# Arduino_Uno_V1_0.net
KiCad netlist of a schematic drawn in Altium Designer
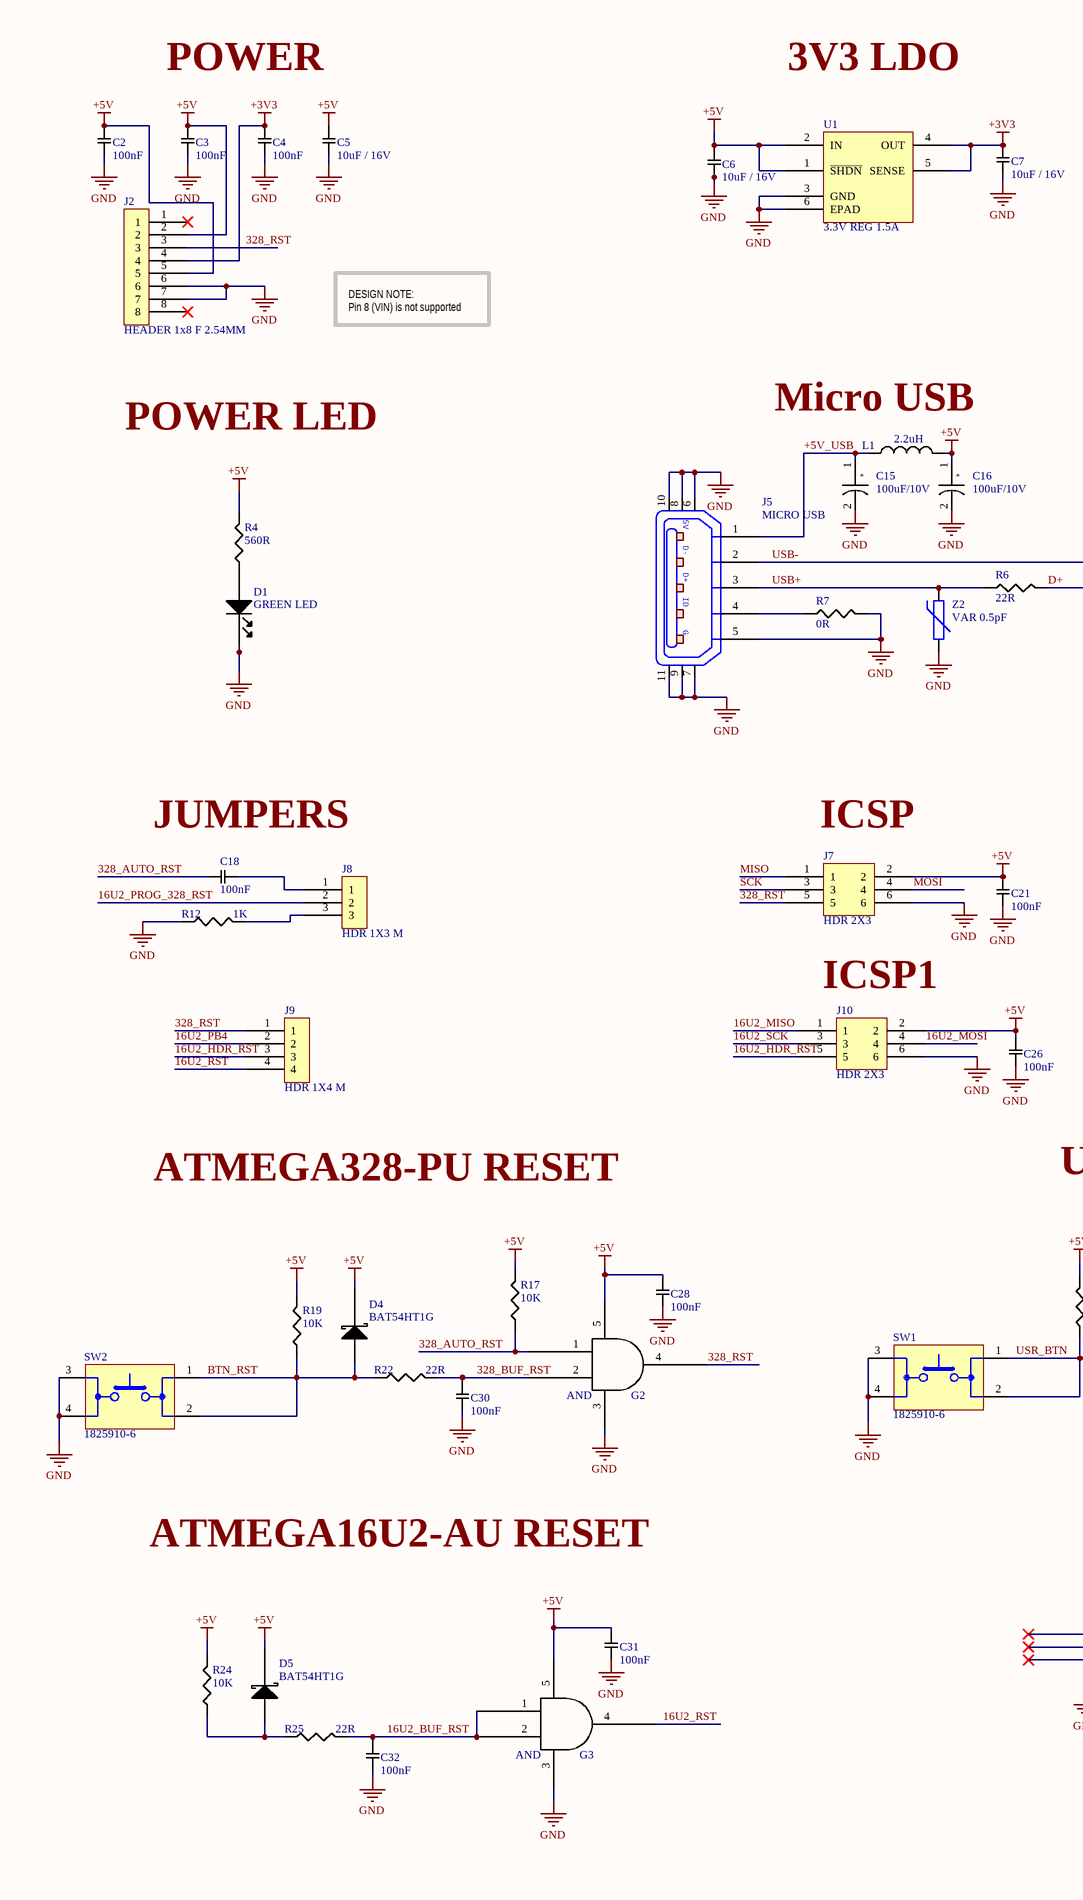
[diagram p0: Arduino_Uno_V1.0.SchDoc, left]
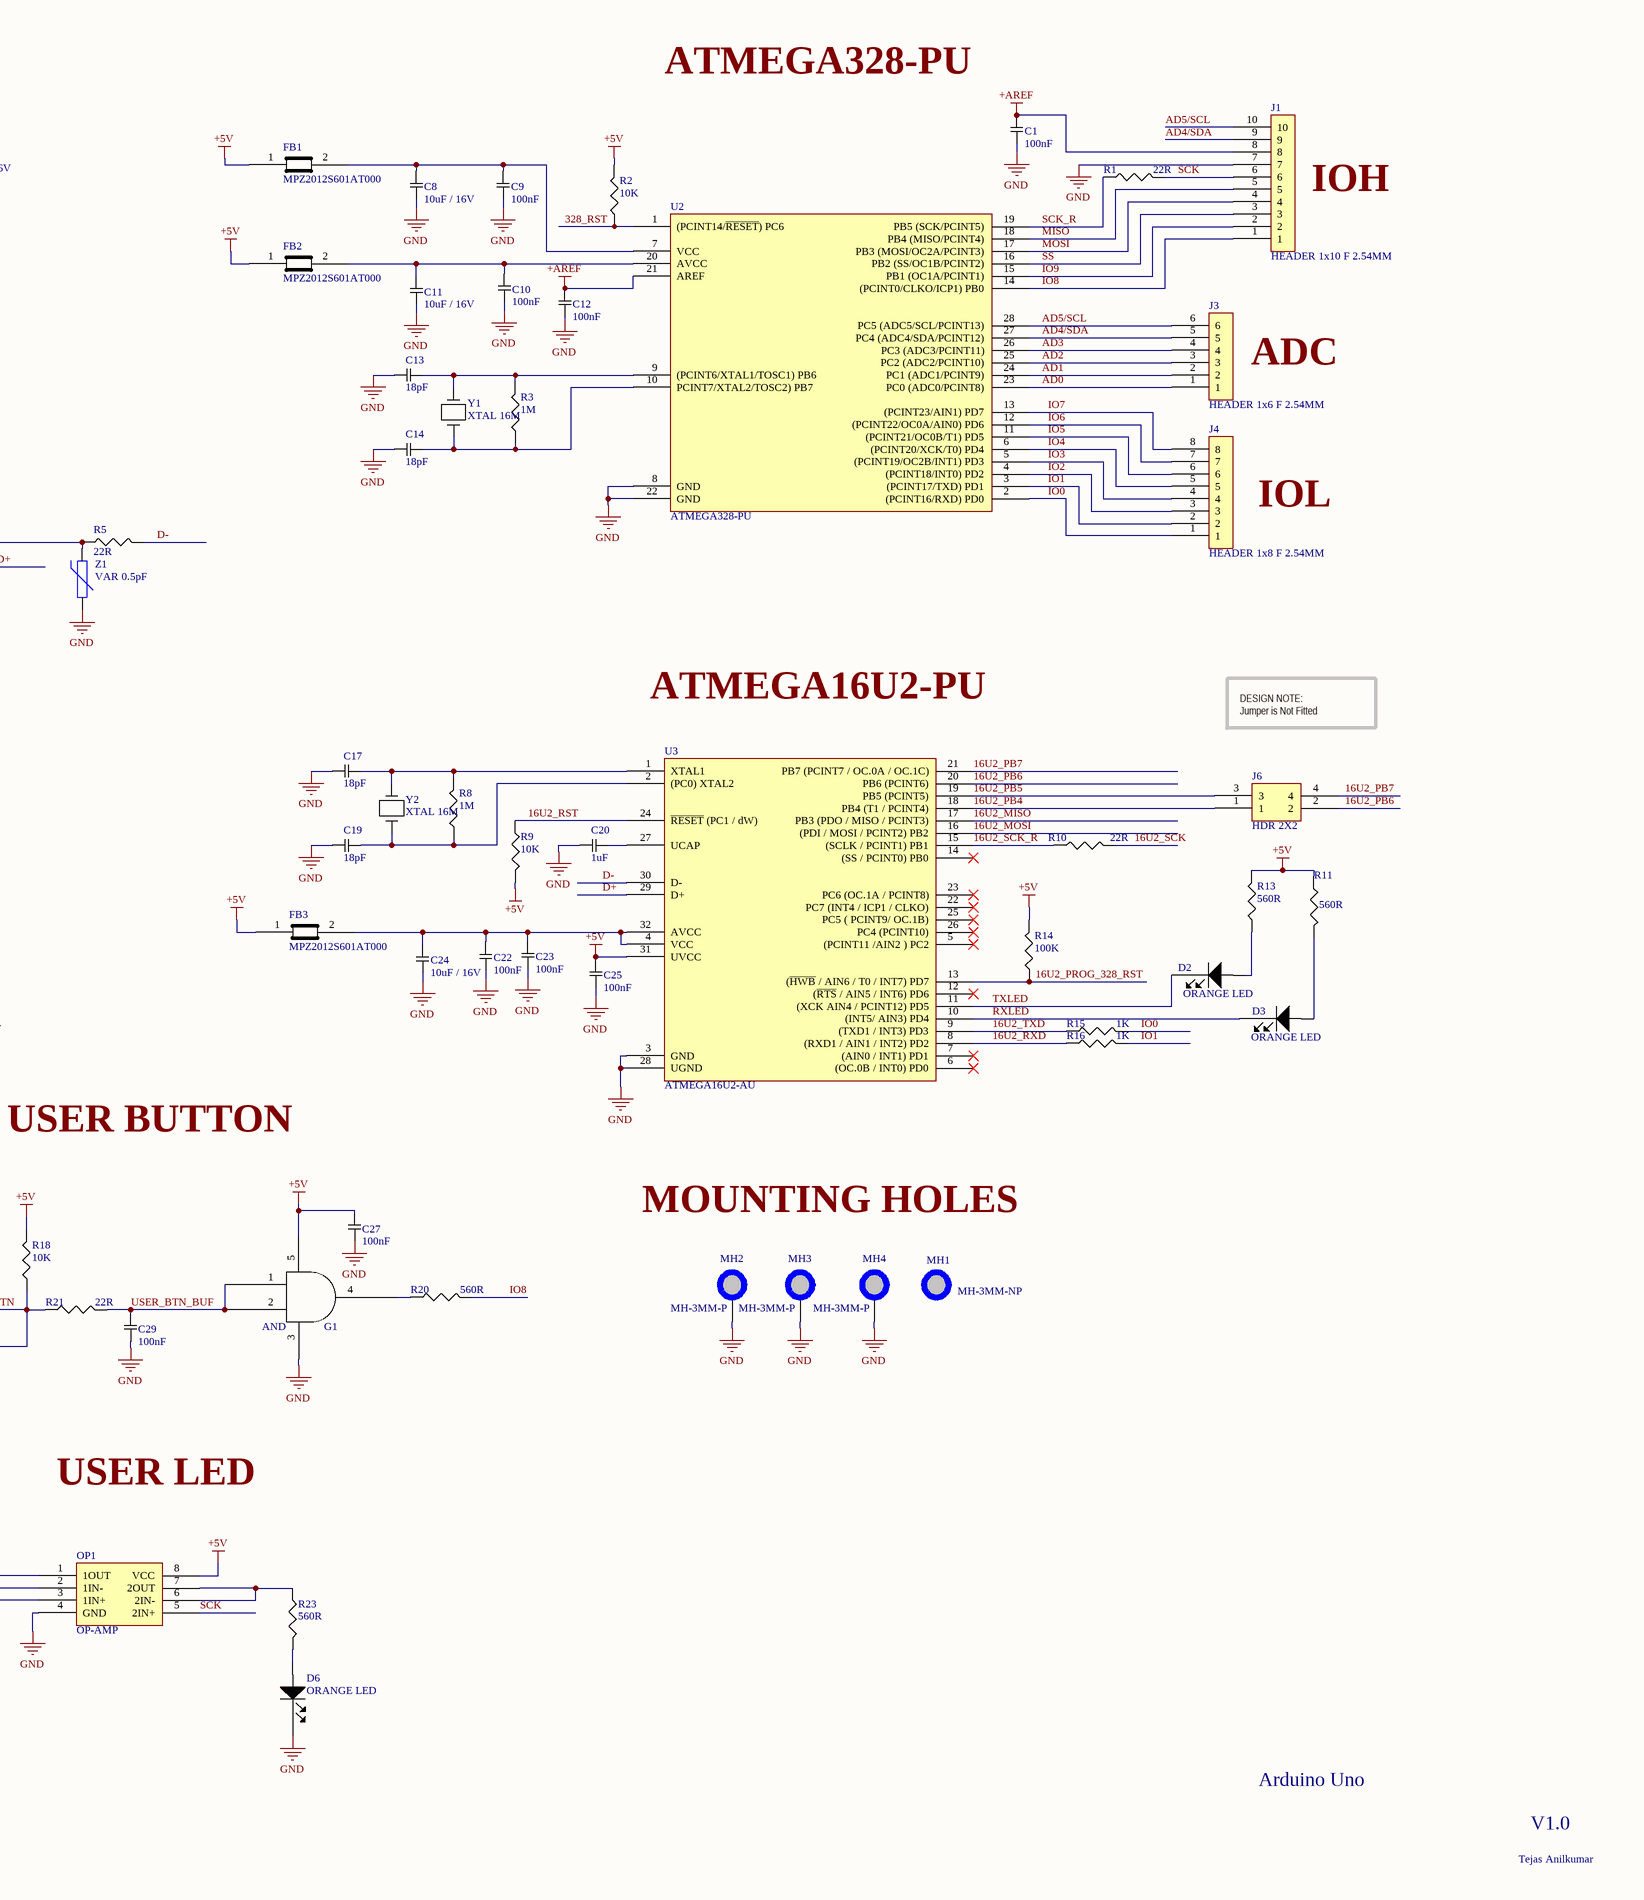
[diagram p1: Arduino_Uno_V1.0.SchDoc, right]

(export (version "E")
  (design (tool "Eeschema 10.0.6"))
  (components
    (comp (ref "C1")
      (value "100nF")
      (footprint "C0805")
      (fields
        (field (name "MANUFACTURER") "TDK")
        (field (name "MANUFACTURER PART NUMBER") "C2012X7R1H104K085AA")
        (field (name "TOLERANCE") "10%")
      )
      (libsource (lib "CAP-100n-0805") (part "C2012X7R1H104K085AA"))
    )
    (comp (ref "C2")
      (value "100nF")
      (footprint "C0805")
      (fields
        (field (name "MANUFACTURER") "TDK")
        (field (name "MANUFACTURER PART NUMBER") "C2012X7R1H104K085AA")
        (field (name "TOLERANCE") "10%")
      )
      (libsource (lib "CAP-100n-0805") (part "C2012X7R1H104K085AA"))
    )
    (comp (ref "C3")
      (value "100nF")
      (footprint "C0805")
      (fields
        (field (name "MANUFACTURER") "TDK")
        (field (name "MANUFACTURER PART NUMBER") "C2012X7R1H104K085AA")
        (field (name "TOLERANCE") "10%")
      )
      (libsource (lib "CAP-100n-0805") (part "C2012X7R1H104K085AA"))
    )
    (comp (ref "C4")
      (value "100nF")
      (footprint "C0805")
      (fields
        (field (name "MANUFACTURER") "TDK")
        (field (name "MANUFACTURER PART NUMBER") "C2012X7R1H104K085AA")
        (field (name "TOLERANCE") "10%")
      )
      (libsource (lib "CAP-100n-0805") (part "C2012X7R1H104K085AA"))
    )
    (comp (ref "C5")
      (value "10uF / 16V")
      (footprint "C0805")
      (fields
        (field (name "MANUFACTURER") "TDK")
        (field (name "MANUFACTURER PART NUMBER") "C2012X5R1C106M125AC")
        (field (name "TOLERANCE") "20%")
      )
      (libsource (lib "CAP-10u-0805") (part "C2012X5R1C106M125AC"))
    )
    (comp (ref "C6")
      (value "10uF / 16V")
      (footprint "C0805")
      (fields
        (field (name "MANUFACTURER") "TDK")
        (field (name "MANUFACTURER PART NUMBER") "C2012X5R1C106M125AC")
        (field (name "TOLERANCE") "20%")
      )
      (libsource (lib "CAP-10u-0805") (part "C2012X5R1C106M125AC"))
    )
    (comp (ref "C7")
      (value "10uF / 16V")
      (footprint "C0805")
      (fields
        (field (name "MANUFACTURER") "TDK")
        (field (name "MANUFACTURER PART NUMBER") "C2012X5R1C106M125AC")
        (field (name "TOLERANCE") "20%")
      )
      (libsource (lib "CAP-10u-0805") (part "C2012X5R1C106M125AC"))
    )
    (comp (ref "C8")
      (value "10uF / 16V")
      (footprint "C0805")
      (fields
        (field (name "MANUFACTURER") "TDK")
        (field (name "MANUFACTURER PART NUMBER") "C2012X5R1C106M125AC")
        (field (name "TOLERANCE") "20%")
      )
      (libsource (lib "CAP-10u-0805") (part "C2012X5R1C106M125AC"))
    )
    (comp (ref "C9")
      (value "100nF")
      (footprint "C0805")
      (fields
        (field (name "MANUFACTURER") "TDK")
        (field (name "MANUFACTURER PART NUMBER") "C2012X7R1H104K085AA")
        (field (name "TOLERANCE") "10%")
      )
      (libsource (lib "CAP-100n-0805") (part "C2012X7R1H104K085AA"))
    )
    (comp (ref "C10")
      (value "100nF")
      (footprint "C0805")
      (fields
        (field (name "MANUFACTURER") "TDK")
        (field (name "MANUFACTURER PART NUMBER") "C2012X7R1H104K085AA")
        (field (name "TOLERANCE") "10%")
      )
      (libsource (lib "CAP-100n-0805") (part "C2012X7R1H104K085AA"))
    )
    (comp (ref "C11")
      (value "10uF / 16V")
      (footprint "C0805")
      (fields
        (field (name "MANUFACTURER") "TDK")
        (field (name "MANUFACTURER PART NUMBER") "C2012X5R1C106M125AC")
        (field (name "TOLERANCE") "20%")
      )
      (libsource (lib "CAP-10u-0805") (part "C2012X5R1C106M125AC"))
    )
    (comp (ref "C12")
      (value "100nF")
      (footprint "C0805")
      (fields
        (field (name "MANUFACTURER") "TDK")
        (field (name "MANUFACTURER PART NUMBER") "C2012X7R1H104K085AA")
        (field (name "TOLERANCE") "10%")
      )
      (libsource (lib "CAP-100n-0805") (part "C2012X7R1H104K085AA"))
    )
    (comp (ref "C13")
      (value "18pF")
      (footprint "C0805")
      (description "CAP CER 18PF 50V C0G/NP0 0805")
      (fields
        (field (name "MANUFACTURER") "KEMET")
        (field (name "MANUFACTURER PART NUMBER") "C0805C180J5GACTU")
      )
      (libsource (lib "CAP-18p-0805") (part "C0805C180J5GACTU"))
    )
    (comp (ref "C14")
      (value "18pF")
      (footprint "C0805")
      (description "CAP CER 18PF 50V C0G/NP0 0805")
      (fields
        (field (name "MANUFACTURER") "KEMET")
        (field (name "MANUFACTURER PART NUMBER") "C0805C180J5GACTU")
      )
      (libsource (lib "CAP-18p-0805") (part "C0805C180J5GACTU"))
    )
    (comp (ref "C15")
      (value "100uF/10V")
      (footprint "CAP-ALUM")
      (description "Cap Aluminum 100uF 10V 20% (5 X 5.4mm) SMD 50mA 1000 hr 85°C T/R")
      (fields
        (field (name "MANUFACTURER") "Panasonic")
        (field (name "MANUFACTURER PART NUMBER") "EEE-1AA101WR")
      )
      (libsource (lib "CAP-100u-POL") (part "EEE-1AA101WR"))
    )
    (comp (ref "C16")
      (value "100uF/10V")
      (footprint "CAP-ALUM")
      (description "Cap Aluminum 100uF 10V 20% (5 X 5.4mm) SMD 50mA 1000 hr 85°C T/R")
      (fields
        (field (name "MANUFACTURER") "Panasonic")
        (field (name "MANUFACTURER PART NUMBER") "EEE-1AA101WR")
      )
      (libsource (lib "CAP-100u-POL") (part "EEE-1AA101WR"))
    )
    (comp (ref "C17")
      (value "18pF")
      (footprint "C0805")
      (description "CAP CER 18PF 50V C0G/NP0 0805")
      (fields
        (field (name "MANUFACTURER") "KEMET")
        (field (name "MANUFACTURER PART NUMBER") "C0805C180J5GACTU")
      )
      (libsource (lib "CAP-18p-0805") (part "C0805C180J5GACTU"))
    )
    (comp (ref "C18")
      (value "100nF")
      (footprint "C0805")
      (fields
        (field (name "MANUFACTURER") "TDK")
        (field (name "MANUFACTURER PART NUMBER") "C2012X7R1H104K085AA")
        (field (name "TOLERANCE") "10%")
      )
      (libsource (lib "CAP-100n-0805") (part "C2012X7R1H104K085AA"))
    )
    (comp (ref "C19")
      (value "18pF")
      (footprint "C0805")
      (description "CAP CER 18PF 50V C0G/NP0 0805")
      (fields
        (field (name "MANUFACTURER") "KEMET")
        (field (name "MANUFACTURER PART NUMBER") "C0805C180J5GACTU")
      )
      (libsource (lib "CAP-18p-0805") (part "C0805C180J5GACTU"))
    )
    (comp (ref "C20")
      (value "1uF")
      (footprint "C0805")
      (fields
        (field (name "MANUFACTURER") "TDK")
        (field (name "MANUFACTURER PART NUMBER") "C2012X5R1E105K125AA")
        (field (name "TOLERANCE") "10%")
      )
      (libsource (lib "CAP-1u-0805") (part "C2012X5R1E105K125AA"))
    )
    (comp (ref "C21")
      (value "100nF")
      (footprint "C0805")
      (fields
        (field (name "MANUFACTURER") "TDK")
        (field (name "MANUFACTURER PART NUMBER") "C2012X7R1H104K085AA")
        (field (name "TOLERANCE") "10%")
      )
      (libsource (lib "CAP-100n-0805") (part "C2012X7R1H104K085AA"))
    )
    (comp (ref "C22")
      (value "100nF")
      (footprint "C0805")
      (fields
        (field (name "MANUFACTURER") "TDK")
        (field (name "MANUFACTURER PART NUMBER") "C2012X7R1H104K085AA")
        (field (name "TOLERANCE") "10%")
      )
      (libsource (lib "CAP-100n-0805") (part "C2012X7R1H104K085AA"))
    )
    (comp (ref "C23")
      (value "100nF")
      (footprint "C0805")
      (fields
        (field (name "MANUFACTURER") "TDK")
        (field (name "MANUFACTURER PART NUMBER") "C2012X7R1H104K085AA")
        (field (name "TOLERANCE") "10%")
      )
      (libsource (lib "CAP-100n-0805") (part "C2012X7R1H104K085AA"))
    )
    (comp (ref "C24")
      (value "10uF / 16V")
      (footprint "C0805")
      (fields
        (field (name "MANUFACTURER") "TDK")
        (field (name "MANUFACTURER PART NUMBER") "C2012X5R1C106M125AC")
        (field (name "TOLERANCE") "20%")
      )
      (libsource (lib "CAP-10u-0805") (part "C2012X5R1C106M125AC"))
    )
    (comp (ref "C25")
      (value "100nF")
      (footprint "C0805")
      (fields
        (field (name "MANUFACTURER") "TDK")
        (field (name "MANUFACTURER PART NUMBER") "C2012X7R1H104K085AA")
        (field (name "TOLERANCE") "10%")
      )
      (libsource (lib "CAP-100n-0805") (part "C2012X7R1H104K085AA"))
    )
    (comp (ref "C26")
      (value "100nF")
      (footprint "C0805")
      (fields
        (field (name "MANUFACTURER") "TDK")
        (field (name "MANUFACTURER PART NUMBER") "C2012X7R1H104K085AA")
        (field (name "TOLERANCE") "10%")
      )
      (libsource (lib "CAP-100n-0805") (part "C2012X7R1H104K085AA"))
    )
    (comp (ref "C27")
      (value "100nF")
      (footprint "C0805")
      (fields
        (field (name "MANUFACTURER") "TDK")
        (field (name "MANUFACTURER PART NUMBER") "C2012X7R1H104K085AA")
        (field (name "TOLERANCE") "10%")
      )
      (libsource (lib "CAP-100n-0805") (part "C2012X7R1H104K085AA"))
    )
    (comp (ref "C28")
      (value "100nF")
      (footprint "C0805")
      (fields
        (field (name "MANUFACTURER") "TDK")
        (field (name "MANUFACTURER PART NUMBER") "C2012X7R1H104K085AA")
        (field (name "TOLERANCE") "10%")
      )
      (libsource (lib "CAP-100n-0805") (part "C2012X7R1H104K085AA"))
    )
    (comp (ref "C29")
      (value "100nF")
      (footprint "C0805")
      (fields
        (field (name "MANUFACTURER") "TDK")
        (field (name "MANUFACTURER PART NUMBER") "C2012X7R1H104K085AA")
        (field (name "TOLERANCE") "10%")
      )
      (libsource (lib "CAP-100n-0805") (part "C2012X7R1H104K085AA"))
    )
    (comp (ref "C30")
      (value "100nF")
      (footprint "C0805")
      (fields
        (field (name "MANUFACTURER") "TDK")
        (field (name "MANUFACTURER PART NUMBER") "C2012X7R1H104K085AA")
        (field (name "TOLERANCE") "10%")
      )
      (libsource (lib "CAP-100n-0805") (part "C2012X7R1H104K085AA"))
    )
    (comp (ref "C31")
      (value "100nF")
      (footprint "C0805")
      (fields
        (field (name "MANUFACTURER") "TDK")
        (field (name "MANUFACTURER PART NUMBER") "C2012X7R1H104K085AA")
        (field (name "TOLERANCE") "10%")
      )
      (libsource (lib "CAP-100n-0805") (part "C2012X7R1H104K085AA"))
    )
    (comp (ref "C32")
      (value "100nF")
      (footprint "C0805")
      (fields
        (field (name "MANUFACTURER") "TDK")
        (field (name "MANUFACTURER PART NUMBER") "C2012X7R1H104K085AA")
        (field (name "TOLERANCE") "10%")
      )
      (libsource (lib "CAP-100n-0805") (part "C2012X7R1H104K085AA"))
    )
    (comp (ref "D1")
      (value "GREEN LED")
      (footprint "LED_0603_GR")
      (description "LED Uni-Color Green 572nm 2-Pin Chip 0603(1608Metric) T/R")
      (fields
        (field (name "MANUFACTURER") "Osram Opto")
        (field (name "MANUFACTURER PART NUMBER") "LGL29K-G2J1-24-Z")
      )
      (libsource (lib "GREEN-LED-SMD") (part "LGL29K-G2J1-24-Z"))
    )
    (comp (ref "D2")
      (value "ORANGE LED")
      (footprint "LED_0603_OR")
      (description "OSRAM - LO L29K-H2K1-24-Z - SMARTLED 0603 ORANGE 55AC2374")
      (fields
        (field (name "MANUFACTURER") "Osram Opto")
        (field (name "MANUFACTURER PART NUMBER") "LOL29K-H2K1-24-Z")
      )
      (libsource (lib "ORANGE-LED-SMD") (part "LOL29K-H2K1-24-Z"))
    )
    (comp (ref "D3")
      (value "ORANGE LED")
      (footprint "LED_0603_OR")
      (description "OSRAM - LO L29K-H2K1-24-Z - SMARTLED 0603 ORANGE 55AC2374")
      (fields
        (field (name "MANUFACTURER") "Osram Opto")
        (field (name "MANUFACTURER PART NUMBER") "LOL29K-H2K1-24-Z")
      )
      (libsource (lib "ORANGE-LED-SMD") (part "LOL29K-H2K1-24-Z"))
    )
    (comp (ref "D4")
      (value "BAT54HT1G")
      (footprint "SOD323")
      (description "Small Signal Schottky Diode, Single, 30 V, 200 Ma, 800 Mv, 600 Ma, 150 C")
      (fields (field (name "MANUFACTURER") "ON Semiconductor / Fairchild"))
      (libsource (lib "SCHOTTKY-DIODE-600mA-30V") (part "BAT54HT1G"))
    )
    (comp (ref "D5")
      (value "BAT54HT1G")
      (footprint "SOD323")
      (description "Small Signal Schottky Diode, Single, 30 V, 200 Ma, 800 Mv, 600 Ma, 150 C")
      (fields (field (name "MANUFACTURER") "ON Semiconductor / Fairchild"))
      (libsource (lib "SCHOTTKY-DIODE-600mA-30V") (part "BAT54HT1G"))
    )
    (comp (ref "D6")
      (value "ORANGE LED")
      (footprint "LED_0603_OR")
      (description "OSRAM - LO L29K-H2K1-24-Z - SMARTLED 0603 ORANGE 55AC2374")
      (fields
        (field (name "MANUFACTURER") "Osram Opto")
        (field (name "MANUFACTURER PART NUMBER") "LOL29K-H2K1-24-Z")
      )
      (libsource (lib "ORANGE-LED-SMD") (part "LOL29K-H2K1-24-Z"))
    )
    (comp (ref "FB1")
      (value "MPZ2012S601AT000")
      (footprint "FERRITE-BEAD-0805")
      (description "Ferrite Beads Multi-Layer Power 600Ohm 25% 100MHz 2A 100mOhm DCR 0805 T/R")
      (fields (field (name "MANUFACTURER") "TDK"))
      (libsource (lib "FERRITE-BEAD-600OHM-0805") (part "MPZ2012S601AT000"))
    )
    (comp (ref "FB2")
      (value "MPZ2012S601AT000")
      (footprint "FERRITE-BEAD-0805")
      (description "Ferrite Beads Multi-Layer Power 600Ohm 25% 100MHz 2A 100mOhm DCR 0805 T/R")
      (fields (field (name "MANUFACTURER") "TDK"))
      (libsource (lib "FERRITE-BEAD-600OHM-0805") (part "MPZ2012S601AT000"))
    )
    (comp (ref "FB3")
      (value "MPZ2012S601AT000")
      (footprint "FERRITE-BEAD-0805")
      (description "Ferrite Beads Multi-Layer Power 600Ohm 25% 100MHz 2A 100mOhm DCR 0805 T/R")
      (fields (field (name "MANUFACTURER") "TDK"))
      (libsource (lib "FERRITE-BEAD-600OHM-0805") (part "MPZ2012S601AT000"))
    )
    (comp (ref "G1")
      (value "AND")
      (footprint "SOT-23-5P")
      (description "TEXAS INSTRUMENTS - SN74AHC1G09DBVR - AND Gate, 74AHC1G09, 2 Input, 2 V to 5.5 V, SOT-23-5")
      (fields
        (field (name "MANUFACTURER") "Texas Instruments")
        (field (name "MANUFACTURER PART NUMBER") "SN74AHC1G09DBVR")
      )
      (libsource (lib "AND-1CH-SOT23") (part "SN74AHC1G09DBVR"))
    )
    (comp (ref "G2")
      (value "AND")
      (footprint "SOT-23-5P")
      (description "TEXAS INSTRUMENTS - SN74AHC1G09DBVR - AND Gate, 74AHC1G09, 2 Input, 2 V to 5.5 V, SOT-23-5")
      (fields
        (field (name "MANUFACTURER") "Texas Instruments")
        (field (name "MANUFACTURER PART NUMBER") "SN74AHC1G09DBVR")
      )
      (libsource (lib "AND-1CH-SOT23") (part "SN74AHC1G09DBVR"))
    )
    (comp (ref "G3")
      (value "AND")
      (footprint "SOT-23-5P")
      (description "TEXAS INSTRUMENTS - SN74AHC1G09DBVR - AND Gate, 74AHC1G09, 2 Input, 2 V to 5.5 V, SOT-23-5")
      (fields
        (field (name "MANUFACTURER") "Texas Instruments")
        (field (name "MANUFACTURER PART NUMBER") "SN74AHC1G09DBVR")
      )
      (libsource (lib "AND-1CH-SOT23") (part "SN74AHC1G09DBVR"))
    )
    (comp (ref "J1")
      (value "HEADER 1x10 F 2.54MM")
      (footprint "HEADER-10F2.54MM")
      (fields (field (name "MANUFACTURER") "Harwin") (field (name "MANUFACTURER PART NUMBER") "M20-7821046"))
      (libsource (lib "HEADER-10PINF-2.54MM") (part "M20-7821046"))
    )
    (comp (ref "J2")
      (value "HEADER 1x8 F 2.54MM")
      (footprint "HDR-1x8-F-2.54MM")
      (description "2.54mm (0.1\") Pitch SIL Vertical PC Tail Socket Assembly, selective gold + tin, 8 contacts")
      (fields (field (name "MANUFACTURER") "Harwin") (field (name "MANUFACTURER PART NUMBER") "M20-7820842"))
      (libsource (lib "HEADER-8PINF-2.54MM") (part "M20-7820842"))
    )
    (comp (ref "J3")
      (value "HEADER 1x6 F 2.54MM")
      (footprint "HEADER-6PINF-2.54MM")
      (description "06-WAY SIL VERT SOCKET L/FREE")
      (fields (field (name "MANUFACTURER") "Harwin") (field (name "MANUFACTURER PART NUMBER") "M20-7820646"))
      (libsource (lib "HEADER-6PINF-2.54MM") (part "M20-7820646"))
    )
    (comp (ref "J4")
      (value "HEADER 1x8 F 2.54MM")
      (footprint "HDR-1x8-F-2.54MM")
      (description "2.54mm (0.1\") Pitch SIL Vertical PC Tail Socket Assembly, selective gold + tin, 8 contacts")
      (fields (field (name "MANUFACTURER") "Harwin") (field (name "MANUFACTURER PART NUMBER") "M20-7820842"))
      (libsource (lib "") (part "M20-7820842_1"))
    )
    (comp (ref "J5")
      (value "MICRO USB")
      (footprint "MICRO-USB")
      (description "CONN USB MICRO B RECPT SMT R/A")
      (fields
        (field (name "MANUFACTURER") "Amphenol ICC / FCI")
        (field (name "MANUFACTURER PART NUMBER") "10118193-0001LF")
      )
      (libsource (lib "MICRO-USB-CONNECTOR") (part "10118193-0001LF"))
    )
    (comp (ref "J6")
      (value "HDR 2X2")
      (footprint "HDR-2X2-2.54MM")
      (description "CONN HEADER 4POS .100 STR 15AU")
      (fields
        (field (name "MANUFACTURER") "Amphenol ICC / FCI")
        (field (name "MANUFACTURER PART NUMBER") "68602-204HLF")
      )
      (libsource (lib "BERGSTIK-4PIN-2R-2.54MM") (part "68602-204HLF"))
    )
    (comp (ref "J7")
      (value "HDR 2X3")
      (footprint "BERGSTIK-2X3-2.54MM")
      (description "Conn Unshrouded Header HDR 6 POS 2.54mm Solder ST Top Entry Thru-Hole BergStik® Bulk")
      (fields
        (field (name "MANUFACTURER") "Amphenol ICC / FCI")
        (field (name "MANUFACTURER PART NUMBER") "67997-106HLF")
      )
      (libsource (lib "BERGSTIK-6PIN-2R-2.54MM") (part "67997-106HLF"))
    )
    (comp (ref "J8")
      (value "HDR 1X3 M")
      (footprint "HDR 3P-M-2.54MM")
      (fields
        (field (name "MANUFACTURER") "Amphenol ICC")
        (field (name "MANUFACTURER PART NUMBER") "68000-103HLF")
      )
      (libsource (lib "HEADER-3PINM-2.54MM") (part "68000-103HLF"))
    )
    (comp (ref "J9")
      (value "HDR 1X4 M")
      (footprint "HDR 1x4 M")
      (description "Conn Unshrouded Header HDR 4 POS 2.54mm Solder ST Thru-Hole Bag")
      (fields
        (field (name "MANUFACTURER") "Amphenol ICC")
        (field (name "MANUFACTURER PART NUMBER") "68001-204HLF")
      )
      (libsource (lib "HEADER-4PINM-2.54MM") (part "68001-204HLF"))
    )
    (comp (ref "J10")
      (value "HDR 2X3")
      (footprint "BERGSTIK-2X3-2.54MM")
      (description "Conn Unshrouded Header HDR 6 POS 2.54mm Solder ST Top Entry Thru-Hole BergStik® Bulk")
      (fields
        (field (name "MANUFACTURER") "Amphenol ICC / FCI")
        (field (name "MANUFACTURER PART NUMBER") "67997-106HLF")
      )
      (libsource (lib "BERGSTIK-6PIN-2R-2.54MM") (part "67997-106HLF"))
    )
    (comp (ref "L1")
      (value "2.2uH")
      (footprint "IND-1210")
      (description "KEMET         L1210R2R2MDWIT             Product Range:L-DWI Series")
      (fields
        (field (name "MANUFACTURER") "KEMET")
        (field (name "MANUFACTURER PART NUMBER") "L1210R2R2MDWIT")
      )
      (libsource (lib "IND-2.2uH-1210") (part "L1210R2R2MDWIT"))
    )
    (comp (ref "MH1")
      (value "MH-3MM-NP")
      (footprint "MH-3MM-NP")
      (description "Mounting Hole 3mm Non-Plated")
      (libsource (lib "MOUNTING-HOLES-NON-PLATED-3MM") (part "MH-3MM NP"))
    )
    (comp (ref "MH2")
      (value "MH-3MM-P")
      (footprint "MH-3MM")
      (description "3MM Mounting Holes Plated")
      (libsource (lib "MOUNTING-HOLES-PLATED-3MM") (part "MH-3MM P"))
    )
    (comp (ref "MH3")
      (value "MH-3MM-P")
      (footprint "MH-3MM")
      (description "3MM Mounting Holes Plated")
      (libsource (lib "MOUNTING-HOLES-PLATED-3MM") (part "MH-3MM P"))
    )
    (comp (ref "MH4")
      (value "MH-3MM-P")
      (footprint "MH-3MM")
      (description "3MM Mounting Holes Plated")
      (libsource (lib "MOUNTING-HOLES-PLATED-3MM") (part "MH-3MM P"))
    )
    (comp (ref "OP1")
      (value "OP-AMP")
      (footprint "SOP8")
      (description "TEXAS INSTRUMENTS - LMV358IDGKR - OP AMP, LOW VOLTAGE, 1MHZ, 1V/US, MSOP-8")
      (fields
        (field (name "MANUFACTURER") "Texas Instruments")
        (field (name "MANUFACTURER PART NUMBER") "LMV358IDGKR")
      )
      (libsource (lib "OPAMP-LMV358-2CH-8PIN") (part "LMV358IDGKR"))
    )
    (comp (ref "R1")
      (value "22R")
      (footprint "R0805")
      (description "RES SMD 22 OHM 1% 1/8W 0805")
      (fields
        (field (name "MANUFACTURER") "Yageo")
        (field (name "MANUFACTURER PART NUMBER") "RC0805FR-0722RL")
      )
      (libsource (lib "RES-22R-0805") (part "RC0805FR-0722RL"))
    )
    (comp (ref "R2")
      (value "10K")
      (footprint "R0805")
      (description "RES SMD 10K OHM 1% 1/8W 0805")
      (fields
        (field (name "MANUFACTURER") "Yageo")
        (field (name "MANUFACTURER PART NUMBER") "RC0805FR-0710KL")
      )
      (libsource (lib "RES-10K-0805") (part "RC0805FR-0710KL"))
    )
    (comp (ref "R3")
      (value "1M")
      (footprint "R0805")
      (description "RES SMD 1M OHM 1% 1/8W 0805")
      (fields
        (field (name "MANUFACTURER") "Yageo")
        (field (name "MANUFACTURER PART NUMBER") "RC0805FR-071ML")
      )
      (libsource (lib "RES-1M-0805") (part "RC0805FR-071ML"))
    )
    (comp (ref "R4")
      (value "560R")
      (footprint "R0805")
      (description "Surface Mount Thick Film Resistor, RC Series, 560 ohm, 125 mW, - 1%, 150 V, 0805 [2012 Metric]")
      (fields
        (field (name "MANUFACTURER") "Yageo")
        (field (name "MANUFACTURER PART NUMBER") "RC0805FR-07560RL")
      )
      (libsource (lib "RES-560R-0805") (part "RC0805FR-07560RL"))
    )
    (comp (ref "R5")
      (value "22R")
      (footprint "R0805")
      (description "RES SMD 22 OHM 1% 1/8W 0805")
      (fields
        (field (name "MANUFACTURER") "Yageo")
        (field (name "MANUFACTURER PART NUMBER") "RC0805FR-0722RL")
      )
      (libsource (lib "RES-22R-0805") (part "RC0805FR-0722RL"))
    )
    (comp (ref "R6")
      (value "22R")
      (footprint "R0805")
      (description "RES SMD 22 OHM 1% 1/8W 0805")
      (fields
        (field (name "MANUFACTURER") "Yageo")
        (field (name "MANUFACTURER PART NUMBER") "RC0805FR-0722RL")
      )
      (libsource (lib "RES-22R-0805") (part "RC0805FR-0722RL"))
    )
    (comp (ref "R7")
      (value "0R")
      (footprint "R0805")
      (description "Surface Mount Thick Film Resistor, RC Series, 125 mW, - 5%, 150 V, 0805 [2012 Metric]")
      (fields
        (field (name "MANUFACTURER") "Yageo")
        (field (name "MANUFACTURER PART NUMBER") "RC0805JR-070RL")
      )
      (libsource (lib "RES-0R-0805") (part "RC0805JR-070RL"))
    )
    (comp (ref "R8")
      (value "1M")
      (footprint "R0805")
      (description "RES SMD 1M OHM 1% 1/8W 0805")
      (fields
        (field (name "MANUFACTURER") "Yageo")
        (field (name "MANUFACTURER PART NUMBER") "RC0805FR-071ML")
      )
      (libsource (lib "RES-1M-0805") (part "RC0805FR-071ML"))
    )
    (comp (ref "R9")
      (value "10K")
      (footprint "R0805")
      (description "RES SMD 10K OHM 1% 1/8W 0805")
      (fields
        (field (name "MANUFACTURER") "Yageo")
        (field (name "MANUFACTURER PART NUMBER") "RC0805FR-0710KL")
      )
      (libsource (lib "RES-10K-0805") (part "RC0805FR-0710KL"))
    )
    (comp (ref "R10")
      (value "22R")
      (footprint "R0805")
      (description "RES SMD 22 OHM 1% 1/8W 0805")
      (fields
        (field (name "MANUFACTURER") "Yageo")
        (field (name "MANUFACTURER PART NUMBER") "RC0805FR-0722RL")
      )
      (libsource (lib "RES-22R-0805") (part "RC0805FR-0722RL"))
    )
    (comp (ref "R11")
      (value "560R")
      (footprint "R0805")
      (description "Surface Mount Thick Film Resistor, RC Series, 560 ohm, 125 mW, - 1%, 150 V, 0805 [2012 Metric]")
      (fields
        (field (name "MANUFACTURER") "Yageo")
        (field (name "MANUFACTURER PART NUMBER") "RC0805FR-07560RL")
      )
      (libsource (lib "RES-560R-0805") (part "RC0805FR-07560RL"))
    )
    (comp (ref "R12")
      (value "1K")
      (footprint "R0805")
      (description "RES SMD 1K OHM 1% 1/8W 0805")
      (fields
        (field (name "MANUFACTURER") "Yageo")
        (field (name "MANUFACTURER PART NUMBER") "RC0805FR-071KL")
      )
      (libsource (lib "RES-1K-0805") (part "RC0805FR-071KL"))
    )
    (comp (ref "R13")
      (value "560R")
      (footprint "R0805")
      (description "Surface Mount Thick Film Resistor, RC Series, 560 ohm, 125 mW, - 1%, 150 V, 0805 [2012 Metric]")
      (fields
        (field (name "MANUFACTURER") "Yageo")
        (field (name "MANUFACTURER PART NUMBER") "RC0805FR-07560RL")
      )
      (libsource (lib "RES-560R-0805") (part "RC0805FR-07560RL"))
    )
    (comp (ref "R14")
      (value "100K")
      (footprint "R0805")
      (description "Res Thick Film 0805 100K Ohm 1% 1/8W ±100ppm/°C Molded SMD Paper T/R")
      (fields
        (field (name "MANUFACTURER") "Yageo")
        (field (name "MANUFACTURER PART NUMBER") "RC0805FR-07100KL")
      )
      (libsource (lib "RES-100K-0805") (part "RC0805FR-07100KL"))
    )
    (comp (ref "R15")
      (value "1K")
      (footprint "R0805")
      (description "RES SMD 1K OHM 1% 1/8W 0805")
      (fields
        (field (name "MANUFACTURER") "Yageo")
        (field (name "MANUFACTURER PART NUMBER") "RC0805FR-071KL")
      )
      (libsource (lib "RES-1K-0805") (part "RC0805FR-071KL"))
    )
    (comp (ref "R16")
      (value "1K")
      (footprint "R0805")
      (description "RES SMD 1K OHM 1% 1/8W 0805")
      (fields
        (field (name "MANUFACTURER") "Yageo")
        (field (name "MANUFACTURER PART NUMBER") "RC0805FR-071KL")
      )
      (libsource (lib "RES-1K-0805") (part "RC0805FR-071KL"))
    )
    (comp (ref "R17")
      (value "10K")
      (footprint "R0805")
      (description "RES SMD 10K OHM 1% 1/8W 0805")
      (fields
        (field (name "MANUFACTURER") "Yageo")
        (field (name "MANUFACTURER PART NUMBER") "RC0805FR-0710KL")
      )
      (libsource (lib "RES-10K-0805") (part "RC0805FR-0710KL"))
    )
    (comp (ref "R18")
      (value "10K")
      (footprint "R0805")
      (description "RES SMD 10K OHM 1% 1/8W 0805")
      (fields
        (field (name "MANUFACTURER") "Yageo")
        (field (name "MANUFACTURER PART NUMBER") "RC0805FR-0710KL")
      )
      (libsource (lib "RES-10K-0805") (part "RC0805FR-0710KL"))
    )
    (comp (ref "R19")
      (value "10K")
      (footprint "R0805")
      (description "RES SMD 10K OHM 1% 1/8W 0805")
      (fields
        (field (name "MANUFACTURER") "Yageo")
        (field (name "MANUFACTURER PART NUMBER") "RC0805FR-0710KL")
      )
      (libsource (lib "RES-10K-0805") (part "RC0805FR-0710KL"))
    )
    (comp (ref "R20")
      (value "560R")
      (footprint "R0805")
      (description "Surface Mount Thick Film Resistor, RC Series, 560 ohm, 125 mW, - 1%, 150 V, 0805 [2012 Metric]")
      (fields
        (field (name "MANUFACTURER") "Yageo")
        (field (name "MANUFACTURER PART NUMBER") "RC0805FR-07560RL")
      )
      (libsource (lib "RES-560R-0805") (part "RC0805FR-07560RL"))
    )
    (comp (ref "R21")
      (value "22R")
      (footprint "R0805")
      (description "RES SMD 22 OHM 1% 1/8W 0805")
      (fields
        (field (name "MANUFACTURER") "Yageo")
        (field (name "MANUFACTURER PART NUMBER") "RC0805FR-0722RL")
      )
      (libsource (lib "RES-22R-0805") (part "RC0805FR-0722RL"))
    )
    (comp (ref "R22")
      (value "22R")
      (footprint "R0805")
      (description "RES SMD 22 OHM 1% 1/8W 0805")
      (fields
        (field (name "MANUFACTURER") "Yageo")
        (field (name "MANUFACTURER PART NUMBER") "RC0805FR-0722RL")
      )
      (libsource (lib "RES-22R-0805") (part "RC0805FR-0722RL"))
    )
    (comp (ref "R23")
      (value "560R")
      (footprint "R0805")
      (description "Surface Mount Thick Film Resistor, RC Series, 560 ohm, 125 mW, - 1%, 150 V, 0805 [2012 Metric]")
      (fields
        (field (name "MANUFACTURER") "Yageo")
        (field (name "MANUFACTURER PART NUMBER") "RC0805FR-07560RL")
      )
      (libsource (lib "RES-560R-0805") (part "RC0805FR-07560RL"))
    )
    (comp (ref "R24")
      (value "10K")
      (footprint "R0805")
      (description "RES SMD 10K OHM 1% 1/8W 0805")
      (fields
        (field (name "MANUFACTURER") "Yageo")
        (field (name "MANUFACTURER PART NUMBER") "RC0805FR-0710KL")
      )
      (libsource (lib "RES-10K-0805") (part "RC0805FR-0710KL"))
    )
    (comp (ref "R25")
      (value "22R")
      (footprint "R0805")
      (description "RES SMD 22 OHM 1% 1/8W 0805")
      (fields
        (field (name "MANUFACTURER") "Yageo")
        (field (name "MANUFACTURER PART NUMBER") "RC0805FR-0722RL")
      )
      (libsource (lib "RES-22R-0805") (part "RC0805FR-0722RL"))
    )
    (comp (ref "SW1")
      (value "1825910-6")
      (footprint "TAC-SW-6X6")
      (description "6X6, H5,  160G TAC.SWITCH")
      (fields (field (name "MANUFACTURER") "TE Connectivity Alcoswitch"))
      (libsource (lib "TAC-SW-6X6MM") (part "1825910-6"))
    )
    (comp (ref "SW2")
      (value "1825910-6")
      (footprint "TAC-SW-6X6")
      (description "6X6, H5,  160G TAC.SWITCH")
      (fields (field (name "MANUFACTURER") "TE Connectivity Alcoswitch"))
      (libsource (lib "TAC-SW-6X6MM") (part "1825910-6"))
    )
    (comp (ref "U1")
      (value "3.3V REG 1.5A")
      (footprint "LDO-DCQ")
      (description "IC REG LINEAR 3.3V 1.5A SOT223-6")
      (fields
        (field (name "MANUFACTURER") "Texas Instruments")
        (field (name "MANUFACTURER PART NUMBER") "TL1963A-33DCQR")
      )
      (libsource (lib "LDO-3.3V-1.5A") (part "TL1963A-33DCQR"))
    )
    (comp (ref "U2")
      (value "ATMEGA328-PU")
      (footprint "ATMEGA328-PU-DIP28 - duplicate")
      (description "MCU 8-bit ATmega AVR RISC 32KB Flash 2.5V/3.3V/5V 28-Pin PDIP")
      (fields (field (name "MANUFACTURER") "Microchip / Atmel"))
      (libsource (lib "ATMEGA328-PU") (part "ATMEGA328-PU"))
    )
    (comp (ref "U3")
      (value "ATMEGA16U2-AU")
      (footprint "TQFP32")
      (description "ATmega Series 16 KB Flash 512 B RAM 16 MHz 8-Bit Microcontroller - TQFP-32")
      (fields (field (name "MANUFACTURER") "Microchip / Atmel"))
      (libsource (lib "ATMEGA16U2-AU-TQFP32") (part "ATMEGA16U2-AU"))
    )
    (comp (ref "Y1")
      (value "XTAL 16M")
      (footprint "XTAL")
      (description "CRYSTAL 16.0000MHZ 18PF SMD")
      (fields
        (field (name "MANUFACTURER") "Abracon")
        (field (name "MANUFACTURER PART NUMBER") "ABM7-16.000MHZ-D2Y-T")
      )
      (libsource (lib "XTAL-16MHZ") (part "ABM7-16.000MHZ-D2Y-T"))
    )
    (comp (ref "Y2")
      (value "XTAL 16M")
      (footprint "XTAL")
      (description "CRYSTAL 16.0000MHZ 18PF SMD")
      (fields
        (field (name "MANUFACTURER") "Abracon")
        (field (name "MANUFACTURER PART NUMBER") "ABM7-16.000MHZ-D2Y-T")
      )
      (libsource (lib "XTAL-16MHZ") (part "ABM7-16.000MHZ-D2Y-T"))
    )
    (comp (ref "Z1")
      (value "VAR 0.5pF")
      (footprint "R0603")
      (description "VARISTOR 0603")
      (fields
        (field (name "MANUFACTURER") "Bourns")
        (field (name "MANUFACTURER PART NUMBER") "CG0603MLC-05E")
      )
      (libsource (lib "VARISTOR-0.5pF-0603") (part "CG0603MLC-05E"))
    )
    (comp (ref "Z2")
      (value "VAR 0.5pF")
      (footprint "R0603")
      (description "VARISTOR 0603")
      (fields
        (field (name "MANUFACTURER") "Bourns")
        (field (name "MANUFACTURER PART NUMBER") "CG0603MLC-05E")
      )
      (libsource (lib "VARISTOR-0.5pF-0603") (part "CG0603MLC-05E"))
    )
  )
  (nets
    (net (code "1") (name "+3V3") (class "Default")
      (node (ref "C4") (pin "2") (pinfunction "2_2") (pintype "passive"))
      (node (ref "C7") (pin "2") (pinfunction "2_2") (pintype "passive"))
      (node (ref "J2") (pin "4") (pinfunction "4_4") (pintype "passive"))
      (node (ref "U1") (pin "4") (pinfunction "OUT_4") (pintype "passive"))
      (node (ref "U1") (pin "5") (pinfunction "SENSE_5") (pintype "passive"))
    )
    (net (code "2") (name "+5V") (class "Default")
      (node (ref "C16") (pin "1") (pinfunction "1_1") (pintype "passive"))
      (node (ref "C2") (pin "2") (pinfunction "2_2") (pintype "passive"))
      (node (ref "C21") (pin "2") (pinfunction "2_2") (pintype "passive"))
      (node (ref "C25") (pin "2") (pinfunction "2_2") (pintype "passive"))
      (node (ref "C26") (pin "2") (pinfunction "2_2") (pintype "passive"))
      (node (ref "C27") (pin "2") (pinfunction "2_2") (pintype "passive"))
      (node (ref "C28") (pin "2") (pinfunction "2_2") (pintype "passive"))
      (node (ref "C3") (pin "2") (pinfunction "2_2") (pintype "passive"))
      (node (ref "C31") (pin "2") (pinfunction "2_2") (pintype "passive"))
      (node (ref "C5") (pin "2") (pinfunction "2_2") (pintype "passive"))
      (node (ref "C6") (pin "2") (pinfunction "2_2") (pintype "passive"))
      (node (ref "D4") (pin "1") (pinfunction "Cathode_1") (pintype "passive"))
      (node (ref "D5") (pin "1") (pinfunction "Cathode_1") (pintype "passive"))
      (node (ref "FB1") (pin "1") (pinfunction "1_1") (pintype "passive"))
      (node (ref "FB2") (pin "1") (pinfunction "1_1") (pintype "passive"))
      (node (ref "FB3") (pin "1") (pinfunction "1_1") (pintype "passive"))
      (node (ref "G1") (pin "5") (pinfunction "VCC_5") (pintype "power_in"))
      (node (ref "G2") (pin "5") (pinfunction "VCC_5") (pintype "power_in"))
      (node (ref "G3") (pin "5") (pinfunction "VCC_5") (pintype "power_in"))
      (node (ref "J10") (pin "2") (pinfunction "2_2") (pintype "passive"))
      (node (ref "J2") (pin "2") (pinfunction "2_2") (pintype "passive"))
      (node (ref "J2") (pin "5") (pinfunction "5_5") (pintype "passive"))
      (node (ref "J7") (pin "2") (pinfunction "2_2") (pintype "passive"))
      (node (ref "L1") (pin "2") (pinfunction "2_2") (pintype "passive"))
      (node (ref "OP1") (pin "8") (pinfunction "VCC_8") (pintype "passive"))
      (node (ref "R11") (pin "1") (pinfunction "1_1") (pintype "passive"))
      (node (ref "R13") (pin "2") (pinfunction "2_2") (pintype "passive"))
      (node (ref "R14") (pin "2") (pinfunction "2_2") (pintype "passive"))
      (node (ref "R17") (pin "2") (pinfunction "2_2") (pintype "passive"))
      (node (ref "R18") (pin "2") (pinfunction "2_2") (pintype "passive"))
      (node (ref "R19") (pin "2") (pinfunction "2_2") (pintype "passive"))
      (node (ref "R2") (pin "2") (pinfunction "2_2") (pintype "passive"))
      (node (ref "R24") (pin "2") (pinfunction "2_2") (pintype "passive"))
      (node (ref "R4") (pin "2") (pinfunction "2_2") (pintype "passive"))
      (node (ref "R9") (pin "2") (pinfunction "2_2") (pintype "passive"))
      (node (ref "U1") (pin "1") (pinfunction "~{SHDN}_1") (pintype "passive"))
      (node (ref "U1") (pin "2") (pinfunction "IN_2") (pintype "passive"))
      (node (ref "U3") (pin "31") (pinfunction "UVCC_31") (pintype "passive"))
    )
    (net (code "3") (name "+AREF") (class "Default")
      (node (ref "C1") (pin "2") (pinfunction "2_2") (pintype "passive"))
      (node (ref "C12") (pin "2") (pinfunction "2_2") (pintype "passive"))
      (node (ref "J1") (pin "8") (pinfunction "8_8") (pintype "passive"))
      (node (ref "U2") (pin "21") (pinfunction "AREF_21") (pintype "passive"))
    )
    (net (code "4") (name "/+5V_USB") (class "Default")
      (node (ref "C15") (pin "1") (pinfunction "1_1") (pintype "passive"))
      (node (ref "J5") (pin "1") (pinfunction "P1_1") (pintype "passive"))
      (node (ref "L1") (pin "1") (pinfunction "1_1") (pintype "passive"))
    )
    (net (code "5") (name "/16U2_BUF_RST") (class "Default")
      (node (ref "C32") (pin "2") (pinfunction "2_2") (pintype "passive"))
      (node (ref "G3") (pin "1") (pinfunction "A_1") (pintype "passive"))
      (node (ref "G3") (pin "2") (pinfunction "B_2") (pintype "passive"))
      (node (ref "R25") (pin "2") (pinfunction "2_2") (pintype "passive"))
    )
    (net (code "6") (name "/16U2_HDR_RST") (class "Default")
      (node (ref "J10") (pin "5") (pinfunction "5_5") (pintype "passive"))
      (node (ref "J9") (pin "3") (pinfunction "3_3") (pintype "passive"))
    )
    (net (code "7") (name "/16U2_MISO") (class "Default")
      (node (ref "J10") (pin "1") (pinfunction "1_1") (pintype "passive"))
      (node (ref "U3") (pin "17") (pinfunction "PB3_(PDO_/_MISO_/_PCINT3)_17") (pintype "passive"))
    )
    (net (code "8") (name "/16U2_MOSI") (class "Default")
      (node (ref "J10") (pin "4") (pinfunction "4_4") (pintype "passive"))
      (node (ref "U3") (pin "16") (pinfunction "(PDI_/_MOSI_/_PCINT2)_PB2_16") (pintype "passive"))
    )
    (net (code "9") (name "/16U2_PB4") (class "Default")
      (node (ref "J6") (pin "1") (pinfunction "1_1") (pintype "passive"))
      (node (ref "J9") (pin "2") (pinfunction "2_2") (pintype "passive"))
      (node (ref "U3") (pin "18") (pinfunction "PB4_(T1_/_PCINT4)_18") (pintype "passive"))
    )
    (net (code "10") (name "/16U2_PB5") (class "Default")
      (node (ref "J6") (pin "3") (pinfunction "3_3") (pintype "passive"))
      (node (ref "U3") (pin "19") (pinfunction "PB5_(PCINT5)_19") (pintype "passive"))
    )
    (net (code "11") (name "/16U2_PB6") (class "Default")
      (node (ref "J6") (pin "2") (pinfunction "2_2") (pintype "passive"))
      (node (ref "U3") (pin "20") (pinfunction "PB6_(PCINT6)_20") (pintype "passive"))
    )
    (net (code "12") (name "/16U2_PB7") (class "Default")
      (node (ref "J6") (pin "4") (pinfunction "4_4") (pintype "passive"))
      (node (ref "U3") (pin "21") (pinfunction "PB7_(PCINT7_/_OC.0A_/_OC.1C)_21") (pintype "passive"))
    )
    (net (code "13") (name "/16U2_PROG_328_RST") (class "Default")
      (node (ref "J8") (pin "2") (pinfunction "2_2") (pintype "passive"))
      (node (ref "R14") (pin "1") (pinfunction "1_1") (pintype "passive"))
      (node (ref "U3") (pin "13") (pinfunction "(~{HWB}_/_AIN6_/_T0_/_INT7)_PD7_13") (pintype "passive"))
    )
    (net (code "14") (name "/16U2_RST") (class "Default")
      (node (ref "G3") (pin "4") (pinfunction "Y_4") (pintype "passive"))
      (node (ref "J9") (pin "4") (pinfunction "4_4") (pintype "passive"))
      (node (ref "R9") (pin "1") (pinfunction "1_1") (pintype "passive"))
      (node (ref "U3") (pin "24") (pinfunction "~{RESET}_(PC1_/_dW)_24") (pintype "passive"))
    )
    (net (code "15") (name "/16U2_RXD") (class "Default")
      (node (ref "R16") (pin "1") (pinfunction "1_1") (pintype "passive"))
      (node (ref "U3") (pin "8") (pinfunction "(RXD1_/_AIN1_/_INT2)_PD2_8") (pintype "passive"))
    )
    (net (code "16") (name "/16U2_SCK") (class "Default")
      (node (ref "J10") (pin "3") (pinfunction "3_3") (pintype "passive"))
      (node (ref "R10") (pin "2") (pinfunction "2_2") (pintype "passive"))
    )
    (net (code "17") (name "/16U2_SCK_R") (class "Default")
      (node (ref "R10") (pin "1") (pinfunction "1_1") (pintype "passive"))
      (node (ref "U3") (pin "15") (pinfunction "(SCLK_/_PCINT1)_PB1_15") (pintype "passive"))
    )
    (net (code "18") (name "/16U2_TXD") (class "Default")
      (node (ref "R15") (pin "1") (pinfunction "1_1") (pintype "passive"))
      (node (ref "U3") (pin "9") (pinfunction "(TXD1_/_INT3)_PD3_9") (pintype "passive"))
    )
    (net (code "19") (name "/328_AUTO_RST") (class "Default")
      (node (ref "C18") (pin "2") (pinfunction "2_2") (pintype "passive"))
      (node (ref "G2") (pin "1") (pinfunction "A_1") (pintype "passive"))
      (node (ref "R17") (pin "1") (pinfunction "1_1") (pintype "passive"))
    )
    (net (code "20") (name "/328_BUF_RST") (class "Default")
      (node (ref "C30") (pin "2") (pinfunction "2_2") (pintype "passive"))
      (node (ref "G2") (pin "2") (pinfunction "B_2") (pintype "passive"))
      (node (ref "R22") (pin "2") (pinfunction "2_2") (pintype "passive"))
    )
    (net (code "21") (name "/328_RST") (class "Default")
      (node (ref "G2") (pin "4") (pinfunction "Y_4") (pintype "passive"))
      (node (ref "J2") (pin "3") (pinfunction "3_3") (pintype "passive"))
      (node (ref "J7") (pin "5") (pinfunction "5_5") (pintype "passive"))
      (node (ref "J9") (pin "1") (pinfunction "1_1") (pintype "passive"))
      (node (ref "R2") (pin "1") (pinfunction "1_1") (pintype "passive"))
      (node (ref "U2") (pin "1") (pinfunction "(PCINT14/~{RESET})_PC6_1") (pintype "passive"))
    )
    (net (code "22") (name "/AD0") (class "Default")
      (node (ref "J3") (pin "1") (pinfunction "1_1") (pintype "passive"))
      (node (ref "U2") (pin "23") (pinfunction "PC0_(ADC0/PCINT8)_23") (pintype "passive"))
    )
    (net (code "23") (name "/AD1") (class "Default")
      (node (ref "J3") (pin "2") (pinfunction "2_2") (pintype "passive"))
      (node (ref "U2") (pin "24") (pinfunction "PC1_(ADC1/PCINT9)_24") (pintype "passive"))
    )
    (net (code "24") (name "/AD2") (class "Default")
      (node (ref "J3") (pin "3") (pinfunction "3_3") (pintype "passive"))
      (node (ref "U2") (pin "25") (pinfunction "PC2_(ADC2/PCINT10)_25") (pintype "passive"))
    )
    (net (code "25") (name "/AD3") (class "Default")
      (node (ref "J3") (pin "4") (pinfunction "4_4") (pintype "passive"))
      (node (ref "U2") (pin "26") (pinfunction "PC3_(ADC3/PCINT11)_26") (pintype "passive"))
    )
    (net (code "26") (name "/AD4{slash}SDA") (class "Default")
      (node (ref "J1") (pin "9") (pinfunction "9_9") (pintype "passive"))
      (node (ref "J3") (pin "5") (pinfunction "5_5") (pintype "passive"))
      (node (ref "U2") (pin "27") (pinfunction "PC4_(ADC4/SDA/PCINT12)_27") (pintype "passive"))
    )
    (net (code "27") (name "/AD5{slash}SCL") (class "Default")
      (node (ref "J1") (pin "10") (pinfunction "10_10") (pintype "passive"))
      (node (ref "J3") (pin "6") (pinfunction "6_6") (pintype "passive"))
      (node (ref "U2") (pin "28") (pinfunction "PC5_(ADC5/SCL/PCINT13)_28") (pintype "passive"))
    )
    (net (code "28") (name "/BTN_RST") (class "Default")
      (node (ref "D4") (pin "2") (pinfunction "Anode_2") (pintype "passive"))
      (node (ref "R19") (pin "1") (pinfunction "1_1") (pintype "passive"))
      (node (ref "R22") (pin "1") (pinfunction "1_1") (pintype "passive"))
      (node (ref "SW2") (pin "1") (pinfunction "1_1") (pintype "passive"))
      (node (ref "SW2") (pin "2") (pinfunction "2_2") (pintype "passive"))
    )
    (net (code "29") (name "/D+") (class "Default")
      (node (ref "R6") (pin "2") (pinfunction "2_2") (pintype "passive"))
      (node (ref "U3") (pin "29") (pinfunction "D+_29") (pintype "passive"))
    )
    (net (code "30") (name "/D-") (class "Default")
      (node (ref "R5") (pin "2") (pinfunction "2_2") (pintype "passive"))
      (node (ref "U3") (pin "30") (pinfunction "D-_30") (pintype "passive"))
    )
    (net (code "31") (name "/IO0") (class "Default")
      (node (ref "J4") (pin "1") (pinfunction "1_1") (pintype "passive"))
      (node (ref "R15") (pin "2") (pinfunction "2_2") (pintype "passive"))
      (node (ref "U2") (pin "2") (pinfunction "(PCINT16/RXD)_PD0_2") (pintype "passive"))
    )
    (net (code "32") (name "/IO1") (class "Default")
      (node (ref "J4") (pin "2") (pinfunction "2_2") (pintype "passive"))
      (node (ref "R16") (pin "2") (pinfunction "2_2") (pintype "passive"))
      (node (ref "U2") (pin "3") (pinfunction "(PCINT17/TXD)_PD1_3") (pintype "passive"))
    )
    (net (code "33") (name "/IO2") (class "Default")
      (node (ref "J4") (pin "3") (pinfunction "3_3") (pintype "passive"))
      (node (ref "U2") (pin "4") (pinfunction "(PCINT18/INT0)_PD2_4") (pintype "passive"))
    )
    (net (code "34") (name "/IO3") (class "Default")
      (node (ref "J4") (pin "4") (pinfunction "4_4") (pintype "passive"))
      (node (ref "U2") (pin "5") (pinfunction "(PCINT19/OC2B/INT1)_PD3_5") (pintype "passive"))
    )
    (net (code "35") (name "/IO4") (class "Default")
      (node (ref "J4") (pin "5") (pinfunction "5_5") (pintype "passive"))
      (node (ref "U2") (pin "6") (pinfunction "(PCINT20/XCK/T0)_PD4_6") (pintype "passive"))
    )
    (net (code "36") (name "/IO5") (class "Default")
      (node (ref "J4") (pin "6") (pinfunction "6_6") (pintype "passive"))
      (node (ref "U2") (pin "11") (pinfunction "(PCINT21/OC0B/T1)_PD5_11") (pintype "passive"))
    )
    (net (code "37") (name "/IO6") (class "Default")
      (node (ref "J4") (pin "7") (pinfunction "7_7") (pintype "passive"))
      (node (ref "U2") (pin "12") (pinfunction "(PCINT22/OC0A/AIN0)_PD6_12") (pintype "passive"))
    )
    (net (code "38") (name "/IO7") (class "Default")
      (node (ref "J4") (pin "8") (pinfunction "8_8") (pintype "passive"))
      (node (ref "U2") (pin "13") (pinfunction "(PCINT23/AIN1)_PD7_13") (pintype "passive"))
    )
    (net (code "39") (name "/IO8") (class "Default")
      (node (ref "J1") (pin "1") (pinfunction "1_1") (pintype "passive"))
      (node (ref "R20") (pin "2") (pinfunction "2_2") (pintype "passive"))
      (node (ref "U2") (pin "14") (pinfunction "(PCINT0/CLKO/ICP1)_PB0_14") (pintype "passive"))
    )
    (net (code "40") (name "/IO9") (class "Default")
      (node (ref "J1") (pin "2") (pinfunction "2_2") (pintype "passive"))
      (node (ref "U2") (pin "15") (pinfunction "PB1_(OC1A/PCINT1)_15") (pintype "passive"))
    )
    (net (code "41") (name "/MISO") (class "Default")
      (node (ref "J1") (pin "5") (pinfunction "5_5") (pintype "passive"))
      (node (ref "J7") (pin "1") (pinfunction "1_1") (pintype "passive"))
      (node (ref "U2") (pin "18") (pinfunction "PB4_(MISO/PCINT4)_18") (pintype "passive"))
    )
    (net (code "42") (name "/MOSI") (class "Default")
      (node (ref "J1") (pin "4") (pinfunction "4_4") (pintype "passive"))
      (node (ref "J7") (pin "4") (pinfunction "4_4") (pintype "passive"))
      (node (ref "U2") (pin "17") (pinfunction "PB3_(MOSI/OC2A/PCINT3)_17") (pintype "passive"))
    )
    (net (code "43") (name "/RXLED") (class "Default")
      (node (ref "D3") (pin "1") (pinfunction "cathode_1") (pintype "passive"))
      (node (ref "U3") (pin "10") (pinfunction "(INT5/_AIN3)_PD4_10") (pintype "passive"))
    )
    (net (code "44") (name "/SCK") (class "Default")
      (node (ref "J1") (pin "6") (pinfunction "6_6") (pintype "passive"))
      (node (ref "J7") (pin "3") (pinfunction "3_3") (pintype "passive"))
      (node (ref "OP1") (pin "5") (pinfunction "2IN+_5") (pintype "passive"))
      (node (ref "R1") (pin "2") (pinfunction "2_2") (pintype "passive"))
    )
    (net (code "45") (name "/SCK_R") (class "Default")
      (node (ref "R1") (pin "1") (pinfunction "1_1") (pintype "passive"))
      (node (ref "U2") (pin "19") (pinfunction "PB5_(SCK/PCINT5)_19") (pintype "passive"))
    )
    (net (code "46") (name "/SS") (class "Default")
      (node (ref "J1") (pin "3") (pinfunction "3_3") (pintype "passive"))
      (node (ref "U2") (pin "16") (pinfunction "PB2_(SS/OC1B/PCINT2)_16") (pintype "passive"))
    )
    (net (code "47") (name "/TXLED") (class "Default")
      (node (ref "D2") (pin "1") (pinfunction "cathode_1") (pintype "passive"))
      (node (ref "U3") (pin "11") (pinfunction "(XCK_AIN4_/_PCINT12)_PD5_11") (pintype "passive"))
    )
    (net (code "48") (name "/USB+") (class "Default")
      (node (ref "J5") (pin "3") (pinfunction "P3_3") (pintype "passive"))
      (node (ref "R6") (pin "1") (pinfunction "1_1") (pintype "passive"))
      (node (ref "Z2") (pin "2") (pinfunction "2_2") (pintype "passive"))
    )
    (net (code "49") (name "/USB-") (class "Default")
      (node (ref "J5") (pin "2") (pinfunction "P2_2") (pintype "passive"))
      (node (ref "R5") (pin "1") (pinfunction "1_1") (pintype "passive"))
      (node (ref "Z1") (pin "2") (pinfunction "2_2") (pintype "passive"))
    )
    (net (code "50") (name "/USER_BTN_BUF") (class "Default")
      (node (ref "C29") (pin "2") (pinfunction "2_2") (pintype "passive"))
      (node (ref "G1") (pin "1") (pinfunction "A_1") (pintype "passive"))
      (node (ref "G1") (pin "2") (pinfunction "B_2") (pintype "passive"))
      (node (ref "R21") (pin "2") (pinfunction "2_2") (pintype "passive"))
    )
    (net (code "51") (name "/USR_BTN") (class "Default")
      (node (ref "R18") (pin "1") (pinfunction "1_1") (pintype "passive"))
      (node (ref "R21") (pin "1") (pinfunction "1_1") (pintype "passive"))
      (node (ref "SW1") (pin "1") (pinfunction "1_1") (pintype "passive"))
      (node (ref "SW1") (pin "2") (pinfunction "2_2") (pintype "passive"))
    )
    (net (code "52") (name "GND") (class "Default")
      (node (ref "C1") (pin "1") (pinfunction "1_1") (pintype "passive"))
      (node (ref "C10") (pin "1") (pinfunction "1_1") (pintype "passive"))
      (node (ref "C11") (pin "1") (pinfunction "1_1") (pintype "passive"))
      (node (ref "C12") (pin "1") (pinfunction "1_1") (pintype "passive"))
      (node (ref "C13") (pin "1") (pinfunction "1_1") (pintype "passive"))
      (node (ref "C14") (pin "1") (pinfunction "1_1") (pintype "passive"))
      (node (ref "C15") (pin "2") (pinfunction "2_2") (pintype "passive"))
      (node (ref "C16") (pin "2") (pinfunction "2_2") (pintype "passive"))
      (node (ref "C17") (pin "1") (pinfunction "1_1") (pintype "passive"))
      (node (ref "C19") (pin "1") (pinfunction "1_1") (pintype "passive"))
      (node (ref "C2") (pin "1") (pinfunction "1_1") (pintype "passive"))
      (node (ref "C20") (pin "1") (pinfunction "1_1") (pintype "passive"))
      (node (ref "C21") (pin "1") (pinfunction "1_1") (pintype "passive"))
      (node (ref "C22") (pin "1") (pinfunction "1_1") (pintype "passive"))
      (node (ref "C23") (pin "1") (pinfunction "1_1") (pintype "passive"))
      (node (ref "C24") (pin "1") (pinfunction "1_1") (pintype "passive"))
      (node (ref "C25") (pin "1") (pinfunction "1_1") (pintype "passive"))
      (node (ref "C26") (pin "1") (pinfunction "1_1") (pintype "passive"))
      (node (ref "C27") (pin "1") (pinfunction "1_1") (pintype "passive"))
      (node (ref "C28") (pin "1") (pinfunction "1_1") (pintype "passive"))
      (node (ref "C29") (pin "1") (pinfunction "1_1") (pintype "passive"))
      (node (ref "C3") (pin "1") (pinfunction "1_1") (pintype "passive"))
      (node (ref "C30") (pin "1") (pinfunction "1_1") (pintype "passive"))
      (node (ref "C31") (pin "1") (pinfunction "1_1") (pintype "passive"))
      (node (ref "C32") (pin "1") (pinfunction "1_1") (pintype "passive"))
      (node (ref "C4") (pin "1") (pinfunction "1_1") (pintype "passive"))
      (node (ref "C5") (pin "1") (pinfunction "1_1") (pintype "passive"))
      (node (ref "C6") (pin "1") (pinfunction "1_1") (pintype "passive"))
      (node (ref "C7") (pin "1") (pinfunction "1_1") (pintype "passive"))
      (node (ref "C8") (pin "1") (pinfunction "1_1") (pintype "passive"))
      (node (ref "C9") (pin "1") (pinfunction "1_1") (pintype "passive"))
      (node (ref "D1") (pin "1") (pinfunction "cathode_1") (pintype "passive"))
      (node (ref "D6") (pin "1") (pinfunction "cathode_1") (pintype "passive"))
      (node (ref "G1") (pin "3") (pinfunction "GND_3") (pintype "power_in"))
      (node (ref "G2") (pin "3") (pinfunction "GND_3") (pintype "power_in"))
      (node (ref "G3") (pin "3") (pinfunction "GND_3") (pintype "power_in"))
      (node (ref "J1") (pin "7") (pinfunction "7_7") (pintype "passive"))
      (node (ref "J10") (pin "6") (pinfunction "6_6") (pintype "passive"))
      (node (ref "J2") (pin "6") (pinfunction "6_6") (pintype "passive"))
      (node (ref "J2") (pin "7") (pinfunction "7_7") (pintype "passive"))
      (node (ref "J5") (pin "10") (pinfunction "10_10") (pintype "passive"))
      (node (ref "J5") (pin "11") (pinfunction "11_11") (pintype "passive"))
      (node (ref "J5") (pin "5") (pinfunction "P5_5") (pintype "passive"))
      (node (ref "J5") (pin "6") (pinfunction "6_6") (pintype "passive"))
      (node (ref "J5") (pin "7") (pinfunction "7_7") (pintype "passive"))
      (node (ref "J5") (pin "8") (pinfunction "8_8") (pintype "passive"))
      (node (ref "J5") (pin "9") (pinfunction "9_9") (pintype "passive"))
      (node (ref "J7") (pin "6") (pinfunction "6_6") (pintype "passive"))
      (node (ref "MH2") (pin "1") (pinfunction "1_1") (pintype "passive"))
      (node (ref "MH3") (pin "1") (pinfunction "1_1") (pintype "passive"))
      (node (ref "MH4") (pin "1") (pinfunction "1_1") (pintype "passive"))
      (node (ref "OP1") (pin "4") (pinfunction "GND_4") (pintype "passive"))
      (node (ref "R12") (pin "1") (pinfunction "1_1") (pintype "passive"))
      (node (ref "R7") (pin "2") (pinfunction "2_2") (pintype "passive"))
      (node (ref "SW1") (pin "3") (pinfunction "MECH1_3") (pintype "passive"))
      (node (ref "SW1") (pin "4") (pinfunction "MECH2_4") (pintype "passive"))
      (node (ref "SW2") (pin "3") (pinfunction "MECH1_3") (pintype "passive"))
      (node (ref "SW2") (pin "4") (pinfunction "MECH2_4") (pintype "passive"))
      (node (ref "U1") (pin "3") (pinfunction "GND_3") (pintype "passive"))
      (node (ref "U1") (pin "6") (pinfunction "EPAD_6") (pintype "passive"))
      (node (ref "U2") (pin "22") (pinfunction "GND_22") (pintype "passive"))
      (node (ref "U2") (pin "8") (pinfunction "GND_8") (pintype "passive"))
      (node (ref "U3") (pin "28") (pinfunction "UGND_28") (pintype "passive"))
      (node (ref "U3") (pin "3") (pinfunction "GND_3") (pintype "passive"))
      (node (ref "Z1") (pin "1") (pinfunction "1_1") (pintype "passive"))
      (node (ref "Z2") (pin "1") (pinfunction "1_1") (pintype "passive"))
    )
    (net (code "53") (name "Net-(C18-Pad1)") (class "Default")
      (node (ref "C18") (pin "1") (pinfunction "1_1") (pintype "passive"))
      (node (ref "J8") (pin "1") (pinfunction "1_1") (pintype "passive"))
    )
    (net (code "54") (name "Net-(D1-ANODE)") (class "Default")
      (node (ref "D1") (pin "2") (pinfunction "ANODE_2") (pintype "passive"))
      (node (ref "R4") (pin "1") (pinfunction "1_1") (pintype "passive"))
    )
    (net (code "55") (name "Net-(D2-ANODE)") (class "Default")
      (node (ref "D2") (pin "2") (pinfunction "ANODE_2") (pintype "passive"))
      (node (ref "R13") (pin "1") (pinfunction "1_1") (pintype "passive"))
    )
    (net (code "56") (name "Net-(D3-ANODE)") (class "Default")
      (node (ref "D3") (pin "2") (pinfunction "ANODE_2") (pintype "passive"))
      (node (ref "R11") (pin "2") (pinfunction "2_2") (pintype "passive"))
    )
    (net (code "57") (name "Net-(D5-Anode)") (class "Default")
      (node (ref "D5") (pin "2") (pinfunction "Anode_2") (pintype "passive"))
      (node (ref "R24") (pin "1") (pinfunction "1_1") (pintype "passive"))
      (node (ref "R25") (pin "1") (pinfunction "1_1") (pintype "passive"))
    )
    (net (code "58") (name "Net-(D6-ANODE)") (class "Default")
      (node (ref "D6") (pin "2") (pinfunction "ANODE_2") (pintype "passive"))
      (node (ref "R23") (pin "2") (pinfunction "2_2") (pintype "passive"))
    )
    (net (code "59") (name "Net-(G1-Y)") (class "Default")
      (node (ref "G1") (pin "4") (pinfunction "Y_4") (pintype "passive"))
      (node (ref "R20") (pin "1") (pinfunction "1_1") (pintype "passive"))
    )
    (net (code "60") (name "Net-(J5-P4)") (class "Default")
      (node (ref "J5") (pin "4") (pinfunction "P4_4") (pintype "passive"))
      (node (ref "R7") (pin "1") (pinfunction "1_1") (pintype "passive"))
    )
    (net (code "61") (name "Net-(J8-Pad3)") (class "Default")
      (node (ref "J8") (pin "3") (pinfunction "3_3") (pintype "passive"))
      (node (ref "R12") (pin "2") (pinfunction "2_2") (pintype "passive"))
    )
    (net (code "62") (name "Net-(OP1-2IN-)") (class "Default")
      (node (ref "OP1") (pin "6") (pinfunction "2IN-_6") (pintype "passive"))
      (node (ref "OP1") (pin "7") (pinfunction "2OUT_7") (pintype "passive"))
      (node (ref "R23") (pin "1") (pinfunction "1_1") (pintype "passive"))
    )
    (net (code "63") (name "Net-(U2-(PCINT6{slash}XTAL1{slash}TOSC1)_PB6)") (class "Default")
      (node (ref "C13") (pin "2") (pinfunction "2_2") (pintype "passive"))
      (node (ref "R3") (pin "2") (pinfunction "2_2") (pintype "passive"))
      (node (ref "U2") (pin "9") (pinfunction "(PCINT6/XTAL1/TOSC1)_PB6_9") (pintype "passive"))
      (node (ref "Y1") (pin "2") (pinfunction "2_2") (pintype "passive"))
    )
    (net (code "64") (name "Net-(U2-AVCC)") (class "Default")
      (node (ref "C10") (pin "2") (pinfunction "2_2") (pintype "passive"))
      (node (ref "C11") (pin "2") (pinfunction "2_2") (pintype "passive"))
      (node (ref "FB2") (pin "2") (pinfunction "2_2") (pintype "passive"))
      (node (ref "U2") (pin "20") (pinfunction "AVCC_20") (pintype "passive"))
    )
    (net (code "65") (name "Net-(U2-PCINT7{slash}XTAL2{slash}TOSC2)_PB7)") (class "Default")
      (node (ref "C14") (pin "2") (pinfunction "2_2") (pintype "passive"))
      (node (ref "R3") (pin "1") (pinfunction "1_1") (pintype "passive"))
      (node (ref "U2") (pin "10") (pinfunction "PCINT7/XTAL2/TOSC2)_PB7_10") (pintype "passive"))
      (node (ref "Y1") (pin "1") (pinfunction "1_1") (pintype "passive"))
    )
    (net (code "66") (name "Net-(U2-VCC)") (class "Default")
      (node (ref "C8") (pin "2") (pinfunction "2_2") (pintype "passive"))
      (node (ref "C9") (pin "2") (pinfunction "2_2") (pintype "passive"))
      (node (ref "FB1") (pin "2") (pinfunction "2_2") (pintype "passive"))
      (node (ref "U2") (pin "7") (pinfunction "VCC_7") (pintype "passive"))
    )
    (net (code "67") (name "Net-(U3-(PC0)_XTAL2)") (class "Default")
      (node (ref "C19") (pin "2") (pinfunction "2_2") (pintype "passive"))
      (node (ref "R8") (pin "1") (pinfunction "1_1") (pintype "passive"))
      (node (ref "U3") (pin "2") (pinfunction "(PC0)_XTAL2_2") (pintype "passive"))
      (node (ref "Y2") (pin "1") (pinfunction "1_1") (pintype "passive"))
    )
    (net (code "68") (name "Net-(U3-AVCC)") (class "Default")
      (node (ref "C22") (pin "2") (pinfunction "2_2") (pintype "passive"))
      (node (ref "C23") (pin "2") (pinfunction "2_2") (pintype "passive"))
      (node (ref "C24") (pin "2") (pinfunction "2_2") (pintype "passive"))
      (node (ref "FB3") (pin "2") (pinfunction "2_2") (pintype "passive"))
      (node (ref "U3") (pin "32") (pinfunction "AVCC_32") (pintype "passive"))
      (node (ref "U3") (pin "4") (pinfunction "VCC_4") (pintype "passive"))
    )
    (net (code "69") (name "Net-(U3-UCAP)") (class "Default")
      (node (ref "C20") (pin "2") (pinfunction "2_2") (pintype "passive"))
      (node (ref "U3") (pin "27") (pinfunction "UCAP_27") (pintype "passive"))
    )
    (net (code "70") (name "Net-(U3-XTAL1)") (class "Default")
      (node (ref "C17") (pin "2") (pinfunction "2_2") (pintype "passive"))
      (node (ref "R8") (pin "2") (pinfunction "2_2") (pintype "passive"))
      (node (ref "U3") (pin "1") (pinfunction "XTAL1_1") (pintype "passive"))
      (node (ref "Y2") (pin "2") (pinfunction "2_2") (pintype "passive"))
    )
    (net (code "71") (name "unconnected-(J2-Pad1)") (class "Default")
      (node (ref "J2") (pin "1") (pinfunction "1_1") (pintype "passive+no_connect"))
    )
    (net (code "72") (name "unconnected-(J2-Pad8)") (class "Default")
      (node (ref "J2") (pin "8") (pinfunction "8_8") (pintype "passive+no_connect"))
    )
    (net (code "73") (name "unconnected-(OP1-1IN+-Pad3)") (class "Default")
      (node (ref "OP1") (pin "3") (pinfunction "1IN+_3") (pintype "passive+no_connect"))
    )
    (net (code "74") (name "unconnected-(OP1-1IN--Pad2)") (class "Default")
      (node (ref "OP1") (pin "2") (pinfunction "1IN-_2") (pintype "passive+no_connect"))
    )
    (net (code "75") (name "unconnected-(OP1-1OUT-Pad1)") (class "Default")
      (node (ref "OP1") (pin "1") (pinfunction "1OUT_1") (pintype "passive+no_connect"))
    )
    (net (code "76") (name "unconnected-(U3-(AIN0_{slash}_INT1)_PD1-Pad7)") (class "Default")
      (node (ref "U3") (pin "7") (pinfunction "(AIN0_/_INT1)_PD1_7") (pintype "passive+no_connect"))
    )
    (net (code "77") (name "unconnected-(U3-(OC.0B_{slash}_INT0)_PD0-Pad6)") (class "Default")
      (node (ref "U3") (pin "6") (pinfunction "(OC.0B_/_INT0)_PD0_6") (pintype "passive+no_connect"))
    )
    (net (code "78") (name "unconnected-(U3-(PCINT11_{slash}AIN2_)_PC2-Pad5)") (class "Default")
      (node (ref "U3") (pin "5") (pinfunction "(PCINT11_/AIN2_)_PC2_5") (pintype "passive+no_connect"))
    )
    (net (code "79") (name "unconnected-(U3-(SS_{slash}_PCINT0)_PB0-Pad14)") (class "Default")
      (node (ref "U3") (pin "14") (pinfunction "(SS_/_PCINT0)_PB0_14") (pintype "passive+no_connect"))
    )
    (net (code "80") (name "unconnected-(U3-(~{RTS}_{slash}_AIN5_{slash}_INT6)_PD6-Pad12)") (class "Default")
      (node (ref "U3") (pin "12") (pinfunction "(~{RTS}_/_AIN5_/_INT6)_PD6_12") (pintype "passive+no_connect"))
    )
    (net (code "81") (name "unconnected-(U3-PC4_(PCINT10)-Pad26)") (class "Default")
      (node (ref "U3") (pin "26") (pinfunction "PC4_(PCINT10)_26") (pintype "passive+no_connect"))
    )
    (net (code "82") (name "unconnected-(U3-PC5_(_PCINT9{slash}_OC.1B)-Pad25)") (class "Default")
      (node (ref "U3") (pin "25") (pinfunction "PC5_(_PCINT9/_OC.1B)_25") (pintype "passive+no_connect"))
    )
    (net (code "83") (name "unconnected-(U3-PC6_(OC.1A_{slash}_PCINT8)-Pad23)") (class "Default")
      (node (ref "U3") (pin "23") (pinfunction "PC6_(OC.1A_/_PCINT8)_23") (pintype "passive+no_connect"))
    )
    (net (code "84") (name "unconnected-(U3-PC7_(INT4_{slash}_ICP1_{slash}_CLKO)-Pad22)") (class "Default")
      (node (ref "U3") (pin "22") (pinfunction "PC7_(INT4_/_ICP1_/_CLKO)_22") (pintype "passive+no_connect"))
    )
  )
)
